# PCB_Design.net
KiCad netlist of a schematic drawn in EAGLE
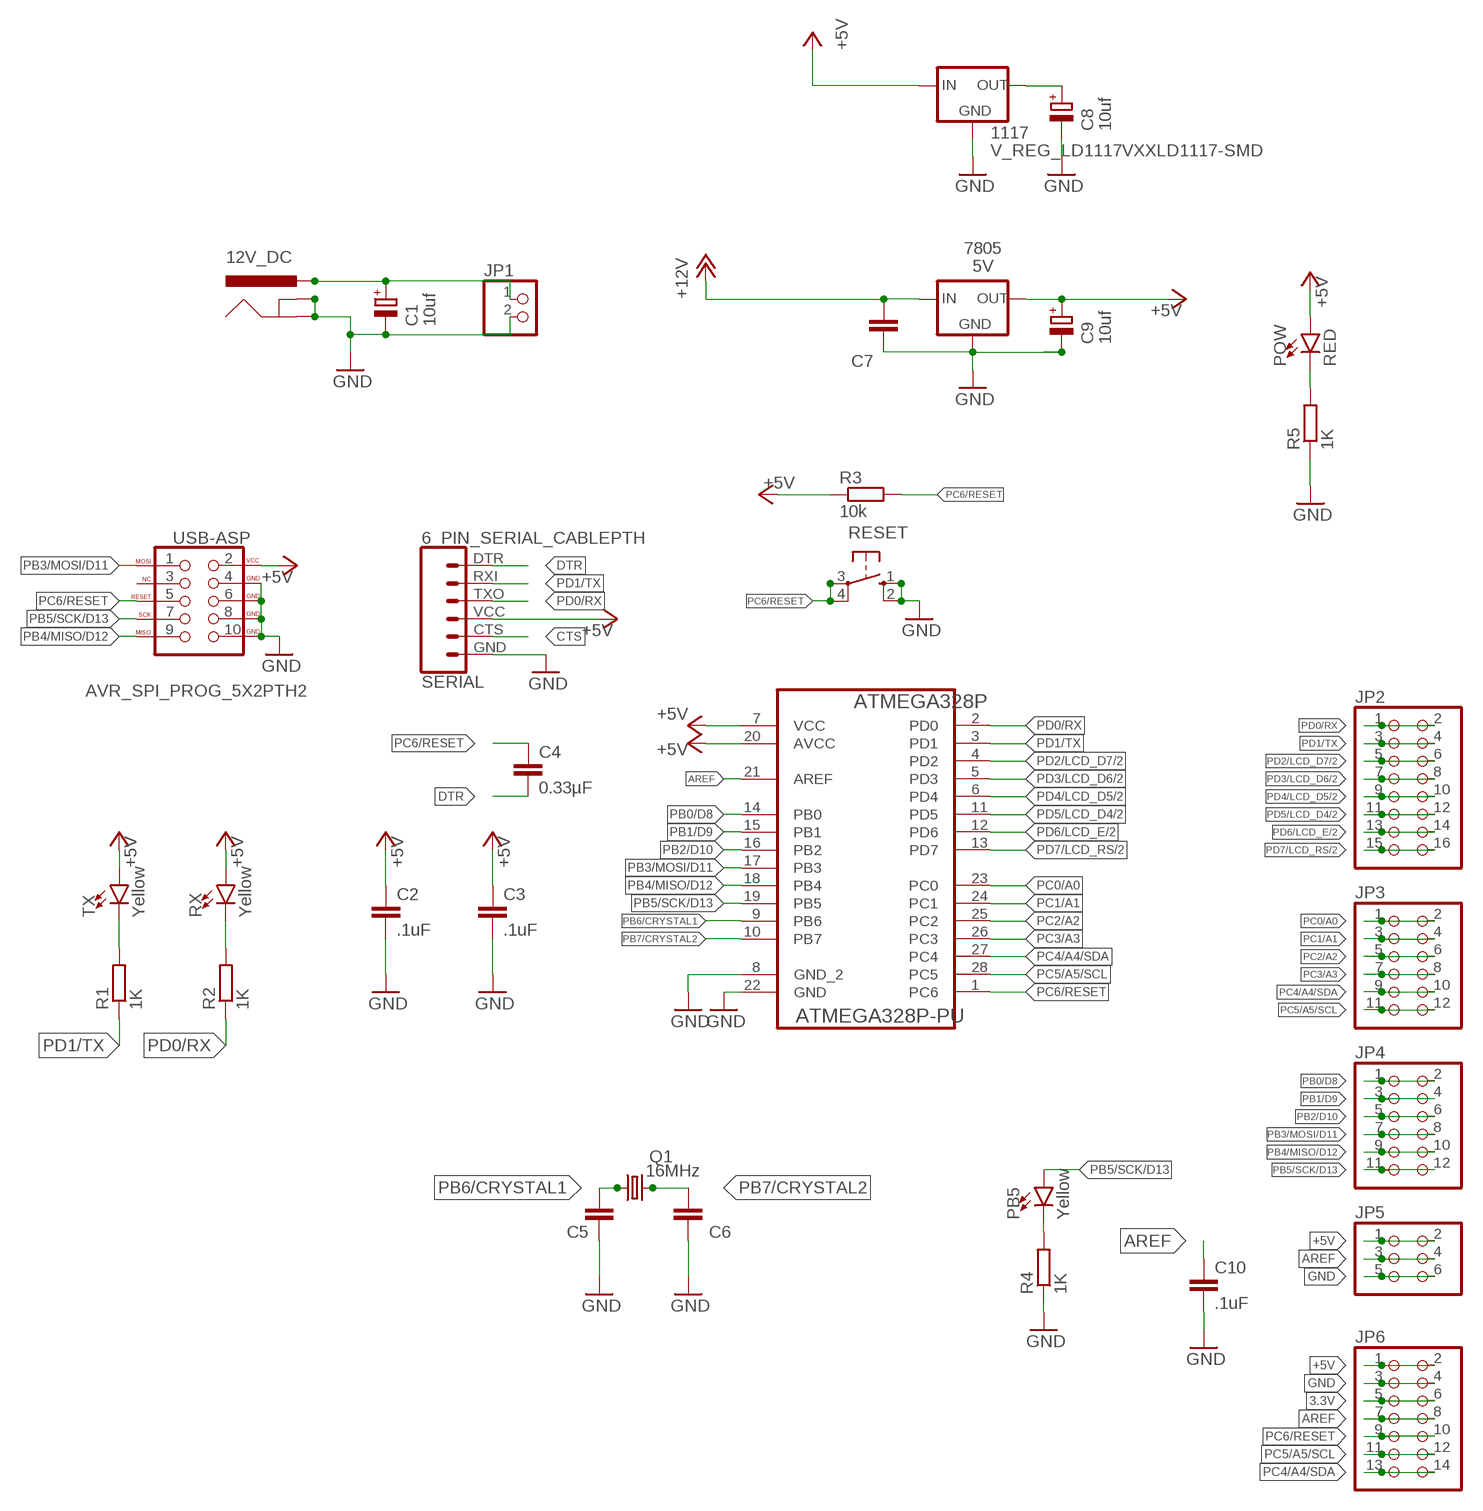
[diagram p0: schematic, sheet 1]
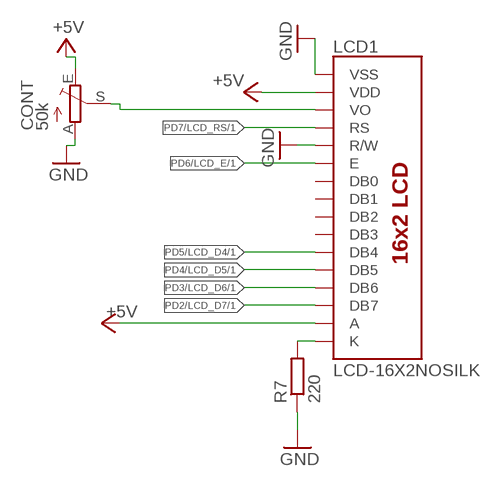
[diagram p1: schematic, sheet 2]

(export (version "E")
  (design (tool "Eeschema 10.0.6"))
  (components
    (comp (ref "CONT")
      (value "50k")
      (footprint "eagle-import:S64W")
      (libsource (lib "eagle-import") (part "TRIM_EU-S64W"))
    )
    (comp (ref "LCD1")
      (value "LCD-16X2NOSILK")
      (footprint "eagle-import:LCD-16X2_NOSILK")
      (libsource (lib "eagle-import") (part "LCD-16X2NOSILK"))
    )
    (comp (ref "R7")
      (value "220")
      (footprint "eagle-import:M0805")
      (libsource (lib "eagle-import") (part "R-EU_M0805"))
    )
    (comp (ref "12V_DC")
      (value "POWER_JACK")
      (footprint "eagle-import:POWER_JACK_PTH")
      (fields (field (name "MF") "MULTICOMP") (field (name "MPN") "SPC21365"))
      (libsource (lib "eagle-import") (part "POWER_JACK"))
    )
    (comp (ref "1117")
      (value "V_REG_LD1117VXXLD1117-SMD")
      (footprint "eagle-import:SOT223")
      (libsource (lib "eagle-import") (part "V_REG_LD1117VXXLD1117-SMD"))
    )
    (comp (ref "7805")
      (value "5V")
      (footprint "eagle-import:TO-252")
      (libsource (lib "eagle-import") (part "V_REG_78XX7812"))
    )
    (comp (ref "ATMEGA328P")
      (value "ATMEGA328P-PU")
      (footprint "eagle-import:DIP254P762X457-28")
      (fields (field (name "MF") "MICROCHIP"))
      (libsource (lib "eagle-import") (part "ATMEGA328P-PU"))
    )
    (comp (ref "C1")
      (value "10uf")
      (footprint "eagle-import:E2,5-6")
      (libsource (lib "eagle-import") (part "CPOL-EUE2.5-6"))
    )
    (comp (ref "C2")
      (value ".1uF")
      (footprint "eagle-import:C0805K")
      (libsource (lib "eagle-import") (part "C-EUC0805K"))
    )
    (comp (ref "C3")
      (value ".1uF")
      (footprint "eagle-import:C0805K")
      (libsource (lib "eagle-import") (part "C-EUC0805K"))
    )
    (comp (ref "C4")
      (value "0.33µF")
      (footprint "eagle-import:C0805K")
      (libsource (lib "eagle-import") (part "C-EUC0805K"))
    )
    (comp (ref "C5")
      (value "22pF")
      (footprint "eagle-import:C0805K")
      (libsource (lib "eagle-import") (part "C-EUC0805K"))
    )
    (comp (ref "C6")
      (value "22pF")
      (footprint "eagle-import:C0805K")
      (libsource (lib "eagle-import") (part "C-EUC0805K"))
    )
    (comp (ref "C7")
      (value ".1uf")
      (footprint "eagle-import:C0805K")
      (libsource (lib "eagle-import") (part "C-EUC0805K"))
    )
    (comp (ref "C8")
      (value "10uf")
      (footprint "eagle-import:E2,5-6")
      (libsource (lib "eagle-import") (part "CPOL-EUE2.5-6"))
    )
    (comp (ref "C9")
      (value "10uf")
      (footprint "eagle-import:E2,5-6")
      (libsource (lib "eagle-import") (part "CPOL-EUE2.5-6"))
    )
    (comp (ref "C10")
      (value ".1uF")
      (footprint "eagle-import:C0805K")
      (libsource (lib "eagle-import") (part "C-EUC0805K"))
    )
    (comp (ref "JP1")
      (value "PINHD-1X2")
      (footprint "eagle-import:1X02")
      (libsource (lib "eagle-import") (part "PINHD-1X2"))
    )
    (comp (ref "JP2")
      (value "PINHD-2X8")
      (footprint "eagle-import:2X08")
      (libsource (lib "eagle-import") (part "PINHD-2X8"))
    )
    (comp (ref "JP3")
      (value "PINHD-2X6")
      (footprint "eagle-import:2X06")
      (libsource (lib "eagle-import") (part "PINHD-2X6"))
    )
    (comp (ref "JP4")
      (value "PINHD-2X6")
      (footprint "eagle-import:2X06")
      (libsource (lib "eagle-import") (part "PINHD-2X6"))
    )
    (comp (ref "JP5")
      (value "PINHD-2X3")
      (footprint "eagle-import:2X03")
      (libsource (lib "eagle-import") (part "PINHD-2X3"))
    )
    (comp (ref "JP6")
      (value "PINHD-2X7")
      (footprint "eagle-import:2X07")
      (libsource (lib "eagle-import") (part "PINHD-2X7"))
    )
    (comp (ref "PB5")
      (value "Yellow")
      (footprint "eagle-import:LED-0603")
      (libsource (lib "eagle-import") (part "LED-BLUE0603"))
    )
    (comp (ref "POW")
      (value "RED")
      (footprint "eagle-import:LED-0603")
      (libsource (lib "eagle-import") (part "LED-BLUE0603"))
    )
    (comp (ref "Q1")
      (value "16MHz")
      (footprint "eagle-import:HC49U70")
      (libsource (lib "eagle-import") (part "CRYSTALHC49U70"))
    )
    (comp (ref "R1")
      (value "1K")
      (footprint "eagle-import:M0805")
      (libsource (lib "eagle-import") (part "R-EU_M0805"))
    )
    (comp (ref "R2")
      (value "1K")
      (footprint "eagle-import:M0805")
      (libsource (lib "eagle-import") (part "R-EU_M0805"))
    )
    (comp (ref "R3")
      (value "10k")
      (footprint "eagle-import:M0805")
      (libsource (lib "eagle-import") (part "R-EU_M0805"))
    )
    (comp (ref "R4")
      (value "1K")
      (footprint "eagle-import:M0805")
      (libsource (lib "eagle-import") (part "R-EU_M0805"))
    )
    (comp (ref "R5")
      (value "1K")
      (footprint "eagle-import:M0805")
      (libsource (lib "eagle-import") (part "R-EU_M0805"))
    )
    (comp (ref "RESET")
      (value "10-XX")
      (footprint "eagle-import:B3F-10XX")
      (fields (field (name "MPN") "B3F-1000") (field (name "MF") "OMRON ELECTRONIC COMPONENTS"))
      (libsource (lib "eagle-import") (part "10-XX"))
    )
    (comp (ref "RX")
      (value "Yellow")
      (footprint "eagle-import:LED-0603")
      (libsource (lib "eagle-import") (part "LED-BLUE0603"))
    )
    (comp (ref "SERIAL")
      (value "6_PIN_SERIAL_CABLEPTH")
      (footprint "eagle-import:FTDI_BASIC")
      (libsource (lib "eagle-import") (part "6_PIN_SERIAL_CABLEPTH"))
    )
    (comp (ref "TX")
      (value "Yellow")
      (footprint "eagle-import:LED-0603")
      (libsource (lib "eagle-import") (part "LED-BLUE0603"))
    )
    (comp (ref "USB-ASP")
      (value "AVR_SPI_PROG_5X2PTH2")
      (footprint "eagle-import:2X5-SHROUDED")
      (libsource (lib "eagle-import") (part "AVR_SPI_PROG_5X2PTH2"))
    )
  )
  (nets
    (net (code "1") (name "+5V") (class "Default")
      (node (ref "1117") (pin "3") (pinfunction "IN_3") (pintype "input"))
      (node (ref "7805") (pin "2") (pinfunction "OUT_2") (pintype "passive"))
      (node (ref "ATMEGA328P") (pin "20") (pinfunction "AVCC_20") (pintype "power_in"))
      (node (ref "ATMEGA328P") (pin "7") (pinfunction "VCC_7") (pintype "power_in"))
      (node (ref "C2") (pin "1") (pinfunction "1_1") (pintype "passive"))
      (node (ref "C3") (pin "1") (pinfunction "1_1") (pintype "passive"))
      (node (ref "C9") (pin "+") (pinfunction "+_+") (pintype "passive"))
      (node (ref "CONT") (pin "E") (pinfunction "E_E") (pintype "passive"))
      (node (ref "JP5") (pin "1") (pinfunction "1_1") (pintype "passive"))
      (node (ref "JP5") (pin "2") (pinfunction "2_2") (pintype "passive"))
      (node (ref "JP6") (pin "1") (pinfunction "1_1") (pintype "passive"))
      (node (ref "JP6") (pin "2") (pinfunction "2_2") (pintype "passive"))
      (node (ref "LCD1") (pin "15") (pinfunction "A_15") (pintype "power_in"))
      (node (ref "LCD1") (pin "2") (pinfunction "VDD_2") (pintype "power_in"))
      (node (ref "POW") (pin "A") (pinfunction "A_A") (pintype "passive"))
      (node (ref "R3") (pin "1") (pinfunction "1_1") (pintype "passive"))
      (node (ref "RX") (pin "A") (pinfunction "A_A") (pintype "passive"))
      (node (ref "SERIAL") (pin "VCC") (pinfunction "4_VCC") (pintype "passive"))
      (node (ref "TX") (pin "A") (pinfunction "A_A") (pintype "passive"))
      (node (ref "USB-ASP") (pin "2") (pinfunction "VCC_2") (pintype "power_in"))
    )
    (net (code "2") (name "+12V") (class "Default")
      (node (ref "12V_DC") (pin "PWR") (pinfunction "PWR_PWR") (pintype "bidirectional"))
      (node (ref "7805") (pin "1") (pinfunction "IN_1") (pintype "input"))
      (node (ref "C1") (pin "+") (pinfunction "+_+") (pintype "passive"))
      (node (ref "C7") (pin "1") (pinfunction "1_1") (pintype "passive"))
      (node (ref "JP1") (pin "1") (pinfunction "1_1") (pintype "passive"))
    )
    (net (code "3") (name "3.3V") (class "Default")
      (node (ref "1117") (pin "2") (pinfunction "OUT_2") (pintype "passive"))
      (node (ref "C8") (pin "+") (pinfunction "+_+") (pintype "passive"))
      (node (ref "JP6") (pin "5") (pinfunction "5_5") (pintype "passive"))
      (node (ref "JP6") (pin "6") (pinfunction "6_6") (pintype "passive"))
    )
    (net (code "4") (name "AREF") (class "Default")
      (node (ref "ATMEGA328P") (pin "21") (pinfunction "AREF_21") (pintype "input"))
      (node (ref "C10") (pin "1") (pinfunction "1_1") (pintype "passive"))
      (node (ref "JP5") (pin "3") (pinfunction "3_3") (pintype "passive"))
      (node (ref "JP5") (pin "4") (pinfunction "4_4") (pintype "passive"))
      (node (ref "JP6") (pin "7") (pinfunction "7_7") (pintype "passive"))
      (node (ref "JP6") (pin "8") (pinfunction "8_8") (pintype "passive"))
    )
    (net (code "5") (name "CTS") (class "Default")
      (node (ref "SERIAL") (pin "CTS") (pinfunction "5_CTS") (pintype "passive"))
    )
    (net (code "6") (name "DTR") (class "Default")
      (node (ref "C4") (pin "2") (pinfunction "2_2") (pintype "passive"))
      (node (ref "SERIAL") (pin "DTR") (pinfunction "1_DTR") (pintype "passive"))
    )
    (net (code "7") (name "GND") (class "Default")
      (node (ref "1117") (pin "1") (pinfunction "GND_1") (pintype "input"))
      (node (ref "12V_DC") (pin "GND") (pinfunction "GND_GND") (pintype "bidirectional"))
      (node (ref "12V_DC") (pin "GNDBREAK") (pinfunction "GNDBREAK_GNDBREAK") (pintype "bidirectional"))
      (node (ref "7805") (pin "3") (pinfunction "GND_3") (pintype "input"))
      (node (ref "ATMEGA328P") (pin "22") (pinfunction "GND_22") (pintype "passive"))
      (node (ref "ATMEGA328P") (pin "8") (pinfunction "GND_2_8") (pintype "passive"))
      (node (ref "C1") (pin "-") (pinfunction "-_-") (pintype "passive"))
      (node (ref "C10") (pin "2") (pinfunction "2_2") (pintype "passive"))
      (node (ref "C2") (pin "2") (pinfunction "2_2") (pintype "passive"))
      (node (ref "C3") (pin "2") (pinfunction "2_2") (pintype "passive"))
      (node (ref "C5") (pin "1") (pinfunction "1_1") (pintype "passive"))
      (node (ref "C6") (pin "1") (pinfunction "1_1") (pintype "passive"))
      (node (ref "C7") (pin "2") (pinfunction "2_2") (pintype "passive"))
      (node (ref "C8") (pin "-") (pinfunction "-_-") (pintype "passive"))
      (node (ref "C9") (pin "-") (pinfunction "-_-") (pintype "passive"))
      (node (ref "CONT") (pin "A") (pinfunction "A_A") (pintype "passive"))
      (node (ref "JP1") (pin "2") (pinfunction "2_2") (pintype "passive"))
      (node (ref "JP5") (pin "5") (pinfunction "5_5") (pintype "passive"))
      (node (ref "JP5") (pin "6") (pinfunction "6_6") (pintype "passive"))
      (node (ref "JP6") (pin "3") (pinfunction "3_3") (pintype "passive"))
      (node (ref "JP6") (pin "4") (pinfunction "4_4") (pintype "passive"))
      (node (ref "LCD1") (pin "1") (pinfunction "VSS_1") (pintype "power_in"))
      (node (ref "LCD1") (pin "5") (pinfunction "R/W_5") (pintype "input"))
      (node (ref "R4") (pin "1") (pinfunction "1_1") (pintype "passive"))
      (node (ref "R5") (pin "1") (pinfunction "1_1") (pintype "passive"))
      (node (ref "R7") (pin "1") (pinfunction "1_1") (pintype "passive"))
      (node (ref "RESET") (pin "1") (pinfunction "S_1") (pintype "passive"))
      (node (ref "RESET") (pin "2") (pinfunction "S1_2") (pintype "passive"))
      (node (ref "SERIAL") (pin "GND") (pinfunction "6_GND") (pintype "passive"))
      (node (ref "USB-ASP") (pin "10") (pinfunction "GND_10") (pintype "power_in"))
      (node (ref "USB-ASP") (pin "4") (pinfunction "GND_4") (pintype "power_in"))
      (node (ref "USB-ASP") (pin "6") (pinfunction "GND_6") (pintype "power_in"))
      (node (ref "USB-ASP") (pin "8") (pinfunction "GND_8") (pintype "power_in"))
    )
    (net (code "8") (name "Net-(LCD1-K)") (class "Default")
      (node (ref "LCD1") (pin "16") (pinfunction "K_16") (pintype "power_in"))
      (node (ref "R7") (pin "2") (pinfunction "2_2") (pintype "passive"))
    )
    (net (code "9") (name "Net-(LCD1-VO)") (class "Default")
      (node (ref "CONT") (pin "S") (pinfunction "S_S") (pintype "passive"))
      (node (ref "LCD1") (pin "3") (pinfunction "VO_3") (pintype "bidirectional"))
    )
    (net (code "10") (name "Net-(PB5-PadC)") (class "Default")
      (node (ref "PB5") (pin "C") (pinfunction "C_C") (pintype "passive"))
      (node (ref "R4") (pin "2") (pinfunction "2_2") (pintype "passive"))
    )
    (net (code "11") (name "Net-(POW-PadC)") (class "Default")
      (node (ref "POW") (pin "C") (pinfunction "C_C") (pintype "passive"))
      (node (ref "R5") (pin "2") (pinfunction "2_2") (pintype "passive"))
    )
    (net (code "12") (name "Net-(R1-Pad2)") (class "Default")
      (node (ref "R1") (pin "2") (pinfunction "2_2") (pintype "passive"))
      (node (ref "TX") (pin "C") (pinfunction "C_C") (pintype "passive"))
    )
    (net (code "13") (name "Net-(R2-Pad2)") (class "Default")
      (node (ref "R2") (pin "2") (pinfunction "2_2") (pintype "passive"))
      (node (ref "RX") (pin "C") (pinfunction "C_C") (pintype "passive"))
    )
    (net (code "14") (name "PB0{slash}D8") (class "Default")
      (node (ref "ATMEGA328P") (pin "14") (pinfunction "PB0_14") (pintype "bidirectional"))
      (node (ref "JP4") (pin "1") (pinfunction "1_1") (pintype "passive"))
      (node (ref "JP4") (pin "2") (pinfunction "2_2") (pintype "passive"))
    )
    (net (code "15") (name "PB1{slash}D9") (class "Default")
      (node (ref "ATMEGA328P") (pin "15") (pinfunction "PB1_15") (pintype "bidirectional"))
      (node (ref "JP4") (pin "3") (pinfunction "3_3") (pintype "passive"))
      (node (ref "JP4") (pin "4") (pinfunction "4_4") (pintype "passive"))
    )
    (net (code "16") (name "PB2{slash}D10") (class "Default")
      (node (ref "ATMEGA328P") (pin "16") (pinfunction "PB2_16") (pintype "bidirectional"))
      (node (ref "JP4") (pin "5") (pinfunction "5_5") (pintype "passive"))
      (node (ref "JP4") (pin "6") (pinfunction "6_6") (pintype "passive"))
    )
    (net (code "17") (name "PB3{slash}MOSI{slash}D11") (class "Default")
      (node (ref "ATMEGA328P") (pin "17") (pinfunction "PB3_17") (pintype "bidirectional"))
      (node (ref "JP4") (pin "7") (pinfunction "7_7") (pintype "passive"))
      (node (ref "JP4") (pin "8") (pinfunction "8_8") (pintype "passive"))
      (node (ref "USB-ASP") (pin "1") (pinfunction "MOSI_1") (pintype "passive"))
    )
    (net (code "18") (name "PB4{slash}MISO{slash}D12") (class "Default")
      (node (ref "ATMEGA328P") (pin "18") (pinfunction "PB4_18") (pintype "bidirectional"))
      (node (ref "JP4") (pin "10") (pinfunction "10_10") (pintype "passive"))
      (node (ref "JP4") (pin "9") (pinfunction "9_9") (pintype "passive"))
      (node (ref "USB-ASP") (pin "9") (pinfunction "MISO_9") (pintype "passive"))
    )
    (net (code "19") (name "PB5{slash}SCK{slash}D13") (class "Default")
      (node (ref "ATMEGA328P") (pin "19") (pinfunction "PB5_19") (pintype "bidirectional"))
      (node (ref "JP4") (pin "11") (pinfunction "11_11") (pintype "passive"))
      (node (ref "JP4") (pin "12") (pinfunction "12_12") (pintype "passive"))
      (node (ref "PB5") (pin "A") (pinfunction "A_A") (pintype "passive"))
      (node (ref "USB-ASP") (pin "7") (pinfunction "SCK_7") (pintype "passive"))
    )
    (net (code "20") (name "PB6{slash}CRYSTAL1") (class "Default")
      (node (ref "ATMEGA328P") (pin "9") (pinfunction "PB6_9") (pintype "bidirectional"))
      (node (ref "C5") (pin "2") (pinfunction "2_2") (pintype "passive"))
      (node (ref "Q1") (pin "1") (pinfunction "1_1") (pintype "passive"))
    )
    (net (code "21") (name "PB7{slash}CRYSTAL2") (class "Default")
      (node (ref "ATMEGA328P") (pin "10") (pinfunction "PB7_10") (pintype "bidirectional"))
      (node (ref "C6") (pin "2") (pinfunction "2_2") (pintype "passive"))
      (node (ref "Q1") (pin "2") (pinfunction "2_2") (pintype "passive"))
    )
    (net (code "22") (name "PC0{slash}A0") (class "Default")
      (node (ref "ATMEGA328P") (pin "23") (pinfunction "PC0_23") (pintype "bidirectional"))
      (node (ref "JP3") (pin "1") (pinfunction "1_1") (pintype "passive"))
      (node (ref "JP3") (pin "2") (pinfunction "2_2") (pintype "passive"))
    )
    (net (code "23") (name "PC1{slash}A1") (class "Default")
      (node (ref "ATMEGA328P") (pin "24") (pinfunction "PC1_24") (pintype "bidirectional"))
      (node (ref "JP3") (pin "3") (pinfunction "3_3") (pintype "passive"))
      (node (ref "JP3") (pin "4") (pinfunction "4_4") (pintype "passive"))
    )
    (net (code "24") (name "PC2{slash}A2") (class "Default")
      (node (ref "ATMEGA328P") (pin "25") (pinfunction "PC2_25") (pintype "bidirectional"))
      (node (ref "JP3") (pin "5") (pinfunction "5_5") (pintype "passive"))
      (node (ref "JP3") (pin "6") (pinfunction "6_6") (pintype "passive"))
    )
    (net (code "25") (name "PC3{slash}A3") (class "Default")
      (node (ref "ATMEGA328P") (pin "26") (pinfunction "PC3_26") (pintype "bidirectional"))
      (node (ref "JP3") (pin "7") (pinfunction "7_7") (pintype "passive"))
      (node (ref "JP3") (pin "8") (pinfunction "8_8") (pintype "passive"))
    )
    (net (code "26") (name "PC4{slash}A4{slash}SDA") (class "Default")
      (node (ref "ATMEGA328P") (pin "27") (pinfunction "PC4_27") (pintype "bidirectional"))
      (node (ref "JP3") (pin "10") (pinfunction "10_10") (pintype "passive"))
      (node (ref "JP3") (pin "9") (pinfunction "9_9") (pintype "passive"))
      (node (ref "JP6") (pin "13") (pinfunction "13_13") (pintype "passive"))
      (node (ref "JP6") (pin "14") (pinfunction "14_14") (pintype "passive"))
    )
    (net (code "27") (name "PC5{slash}A5{slash}SCL") (class "Default")
      (node (ref "ATMEGA328P") (pin "28") (pinfunction "PC5_28") (pintype "bidirectional"))
      (node (ref "JP3") (pin "11") (pinfunction "11_11") (pintype "passive"))
      (node (ref "JP3") (pin "12") (pinfunction "12_12") (pintype "passive"))
      (node (ref "JP6") (pin "11") (pinfunction "11_11") (pintype "passive"))
      (node (ref "JP6") (pin "12") (pinfunction "12_12") (pintype "passive"))
    )
    (net (code "28") (name "PC6{slash}RESET") (class "Default")
      (node (ref "ATMEGA328P") (pin "1") (pinfunction "PC6_1") (pintype "bidirectional"))
      (node (ref "C4") (pin "1") (pinfunction "1_1") (pintype "passive"))
      (node (ref "JP6") (pin "10") (pinfunction "10_10") (pintype "passive"))
      (node (ref "JP6") (pin "9") (pinfunction "9_9") (pintype "passive"))
      (node (ref "R3") (pin "2") (pinfunction "2_2") (pintype "passive"))
      (node (ref "RESET") (pin "3") (pinfunction "P_3") (pintype "passive"))
      (node (ref "RESET") (pin "4") (pinfunction "P1_4") (pintype "passive"))
      (node (ref "USB-ASP") (pin "5") (pinfunction "RESET_5") (pintype "passive"))
    )
    (net (code "29") (name "PD0{slash}RX") (class "Default")
      (node (ref "ATMEGA328P") (pin "2") (pinfunction "PD0_2") (pintype "bidirectional"))
      (node (ref "JP2") (pin "1") (pinfunction "1_1") (pintype "passive"))
      (node (ref "JP2") (pin "2") (pinfunction "2_2") (pintype "passive"))
      (node (ref "R2") (pin "1") (pinfunction "1_1") (pintype "passive"))
      (node (ref "SERIAL") (pin "TXO") (pinfunction "3_TXO") (pintype "passive"))
    )
    (net (code "30") (name "PD1{slash}TX") (class "Default")
      (node (ref "ATMEGA328P") (pin "3") (pinfunction "PD1_3") (pintype "bidirectional"))
      (node (ref "JP2") (pin "3") (pinfunction "3_3") (pintype "passive"))
      (node (ref "JP2") (pin "4") (pinfunction "4_4") (pintype "passive"))
      (node (ref "R1") (pin "1") (pinfunction "1_1") (pintype "passive"))
      (node (ref "SERIAL") (pin "RXI") (pinfunction "2_RXI") (pintype "passive"))
    )
    (net (code "31") (name "PD2{slash}LCD_D7") (class "Default")
      (node (ref "ATMEGA328P") (pin "4") (pinfunction "PD2_4") (pintype "bidirectional"))
      (node (ref "JP2") (pin "5") (pinfunction "5_5") (pintype "passive"))
      (node (ref "JP2") (pin "6") (pinfunction "6_6") (pintype "passive"))
      (node (ref "LCD1") (pin "14") (pinfunction "DB7_14") (pintype "bidirectional"))
    )
    (net (code "32") (name "PD3{slash}LCD_D6") (class "Default")
      (node (ref "ATMEGA328P") (pin "5") (pinfunction "PD3_5") (pintype "bidirectional"))
      (node (ref "JP2") (pin "7") (pinfunction "7_7") (pintype "passive"))
      (node (ref "JP2") (pin "8") (pinfunction "8_8") (pintype "passive"))
      (node (ref "LCD1") (pin "13") (pinfunction "DB6_13") (pintype "bidirectional"))
    )
    (net (code "33") (name "PD4{slash}LCD_D5") (class "Default")
      (node (ref "ATMEGA328P") (pin "6") (pinfunction "PD4_6") (pintype "bidirectional"))
      (node (ref "JP2") (pin "10") (pinfunction "10_10") (pintype "passive"))
      (node (ref "JP2") (pin "9") (pinfunction "9_9") (pintype "passive"))
      (node (ref "LCD1") (pin "12") (pinfunction "DB5_12") (pintype "bidirectional"))
    )
    (net (code "34") (name "PD5{slash}LCD_D4") (class "Default")
      (node (ref "ATMEGA328P") (pin "11") (pinfunction "PD5_11") (pintype "bidirectional"))
      (node (ref "JP2") (pin "11") (pinfunction "11_11") (pintype "passive"))
      (node (ref "JP2") (pin "12") (pinfunction "12_12") (pintype "passive"))
      (node (ref "LCD1") (pin "11") (pinfunction "DB4_11") (pintype "bidirectional"))
    )
    (net (code "35") (name "PD6{slash}LCD_E") (class "Default")
      (node (ref "ATMEGA328P") (pin "12") (pinfunction "PD6_12") (pintype "bidirectional"))
      (node (ref "JP2") (pin "13") (pinfunction "13_13") (pintype "passive"))
      (node (ref "JP2") (pin "14") (pinfunction "14_14") (pintype "passive"))
      (node (ref "LCD1") (pin "6") (pinfunction "E_6") (pintype "input"))
    )
    (net (code "36") (name "PD7{slash}LCD_RS") (class "Default")
      (node (ref "ATMEGA328P") (pin "13") (pinfunction "PD7_13") (pintype "bidirectional"))
      (node (ref "JP2") (pin "15") (pinfunction "15_15") (pintype "passive"))
      (node (ref "JP2") (pin "16") (pinfunction "16_16") (pintype "passive"))
      (node (ref "LCD1") (pin "4") (pinfunction "RS_4") (pintype "input"))
    )
    (net (code "37") (name "unconnected-(LCD1-DB0-Pad7)") (class "Default")
      (node (ref "LCD1") (pin "7") (pinfunction "DB0_7") (pintype "bidirectional"))
    )
    (net (code "38") (name "unconnected-(LCD1-DB1-Pad8)") (class "Default")
      (node (ref "LCD1") (pin "8") (pinfunction "DB1_8") (pintype "bidirectional"))
    )
    (net (code "39") (name "unconnected-(LCD1-DB2-Pad9)") (class "Default")
      (node (ref "LCD1") (pin "9") (pinfunction "DB2_9") (pintype "bidirectional"))
    )
    (net (code "40") (name "unconnected-(LCD1-DB3-Pad10)") (class "Default")
      (node (ref "LCD1") (pin "10") (pinfunction "DB3_10") (pintype "bidirectional"))
    )
    (net (code "41") (name "unconnected-(USB-ASP-NC-Pad3)") (class "Default")
      (node (ref "USB-ASP") (pin "3") (pinfunction "NC_3") (pintype "no_connect"))
    )
  )
)
